# led_saber.net
KiCad netlist of a schematic drawn in EAGLE
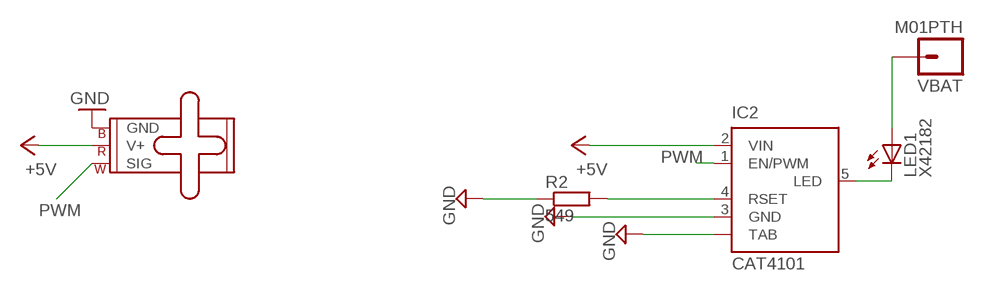
[diagram p0: schematic, sheet 1]

(export (version "E")
  (design (tool "Eeschema 10.0.6"))
  (components
    (comp (ref "IC2")
      (value "CAT4101")
      (footprint "eagle-import:TO263_5")
      (fields (field (name "MPN") "CAT4101TV-T75"))
      (libsource (lib "eagle-import") (part "CAT4101"))
    )
    (comp (ref "LED")
      (value "SMALL_SERVO")
      (footprint "eagle-import:1X03")
      (libsource (lib "eagle-import") (part "SMALL_SERVO"))
    )
    (comp (ref "LED1")
      (value "X42182")
      (footprint "eagle-import:Z-POWER-LED-DOME-TYPE")
      (libsource (lib "eagle-import") (part "X42182"))
    )
    (comp (ref "R2")
      (value "549")
      (footprint "eagle-import:R0805")
      (libsource (lib "eagle-import") (part "R-EU_R0805"))
    )
    (comp (ref "VBAT")
      (value "M01PTH")
      (footprint "eagle-import:1X01")
      (libsource (lib "eagle-import") (part "M01PTH"))
    )
  )
  (nets
    (net (code "1") (name "+5V") (class "Default")
      (node (ref "IC2") (pin "2") (pinfunction "VIN_2") (pintype "input"))
      (node (ref "LED") (pin "2") (pinfunction "V+_2") (pintype "bidirectional"))
    )
    (net (code "2") (name "/PWM") (class "Default")
      (node (ref "IC2") (pin "1") (pinfunction "EN/PWM_1") (pintype "input"))
      (node (ref "LED") (pin "1") (pinfunction "SIG_1") (pintype "bidirectional"))
    )
    (net (code "3") (name "GND") (class "Default")
      (node (ref "IC2") (pin "3") (pinfunction "GND_3") (pintype "power_in"))
      (node (ref "IC2") (pin "TAB") (pinfunction "TAB_TAB") (pintype "passive"))
      (node (ref "LED") (pin "3") (pinfunction "GND_3") (pintype "bidirectional"))
      (node (ref "R2") (pin "1") (pinfunction "1_1") (pintype "passive"))
    )
    (net (code "4") (name "Net-(IC2-LED)") (class "Default")
      (node (ref "IC2") (pin "5") (pinfunction "LED_5") (pintype "power_in"))
      (node (ref "LED1") (pin "C") (pinfunction "C_C") (pintype "passive"))
    )
    (net (code "5") (name "Net-(IC2-RSET)") (class "Default")
      (node (ref "IC2") (pin "4") (pinfunction "RSET_4") (pintype "input"))
      (node (ref "R2") (pin "2") (pinfunction "2_2") (pintype "passive"))
    )
    (net (code "6") (name "Net-(LED1-PadA)") (class "Default")
      (node (ref "LED1") (pin "A") (pinfunction "A_A") (pintype "passive"))
      (node (ref "VBAT") (pin "1") (pinfunction "1_1") (pintype "passive"))
    )
  )
)
